# OutputDigital.net
KiCad netlist of a schematic drawn in Altium Designer
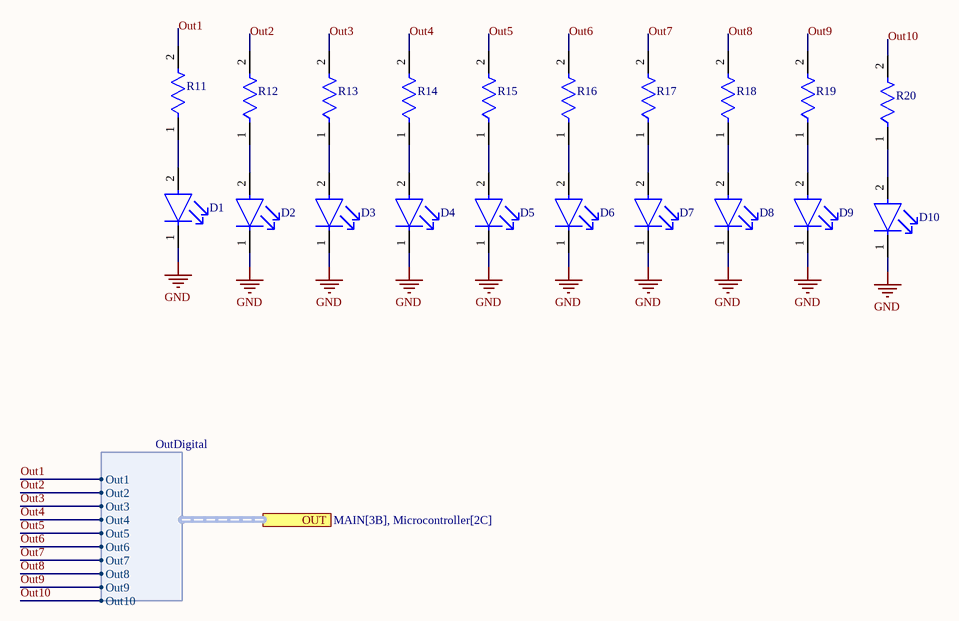
[diagram p0: OutputDigital.SchDoc]

(export (version "E")
  (design (tool "Eeschema 10.0.6"))
  (components
    (comp (ref "D1")
      (value "LTST-C230KRKT")
      (footprint "FP-LTST-C230KRKT-MFG")
      (description "LED RED CLEAR CHIP SMD")
      (libsource (lib "Ejemplo2") (part "CMP-22017-000041-1"))
    )
    (comp (ref "D2")
      (value "LTST-C230KRKT")
      (footprint "FP-LTST-C230KRKT-MFG")
      (description "LED RED CLEAR CHIP SMD")
      (libsource (lib "Ejemplo2") (part "CMP-22017-000041-1"))
    )
    (comp (ref "D3")
      (value "LTST-C230KRKT")
      (footprint "FP-LTST-C230KRKT-MFG")
      (description "LED RED CLEAR CHIP SMD")
      (libsource (lib "Ejemplo2") (part "CMP-22017-000041-1"))
    )
    (comp (ref "D4")
      (value "LTST-C230KRKT")
      (footprint "FP-LTST-C230KRKT-MFG")
      (description "LED RED CLEAR CHIP SMD")
      (libsource (lib "Ejemplo2") (part "CMP-22017-000041-1"))
    )
    (comp (ref "D5")
      (value "LTST-C230KRKT")
      (footprint "FP-LTST-C230KRKT-MFG")
      (description "LED RED CLEAR CHIP SMD")
      (libsource (lib "Ejemplo2") (part "CMP-22017-000041-1"))
    )
    (comp (ref "D6")
      (value "LTST-C230KRKT")
      (footprint "FP-LTST-C230KRKT-MFG")
      (description "LED RED CLEAR CHIP SMD")
      (libsource (lib "Ejemplo2") (part "CMP-22017-000041-1"))
    )
    (comp (ref "D7")
      (value "LTST-C230KRKT")
      (footprint "FP-LTST-C230KRKT-MFG")
      (description "LED RED CLEAR CHIP SMD")
      (libsource (lib "Ejemplo2") (part "CMP-22017-000041-1"))
    )
    (comp (ref "D8")
      (value "LTST-C230KRKT")
      (footprint "FP-LTST-C230KRKT-MFG")
      (description "LED RED CLEAR CHIP SMD")
      (libsource (lib "Ejemplo2") (part "CMP-22017-000041-1"))
    )
    (comp (ref "D9")
      (value "LTST-C230KRKT")
      (footprint "FP-LTST-C230KRKT-MFG")
      (description "LED RED CLEAR CHIP SMD")
      (libsource (lib "Ejemplo2") (part "CMP-22017-000041-1"))
    )
    (comp (ref "D10")
      (value "LTST-C230KRKT")
      (footprint "FP-LTST-C230KRKT-MFG")
      (description "LED RED CLEAR CHIP SMD")
      (libsource (lib "Ejemplo2") (part "CMP-22017-000041-1"))
    )
    (comp (ref "R11")
      (value "RT0805BRD07249RL")
      (footprint "FP-RT0805-MFG")
      (description "RES SMD 249 OHM 0.1% 1/8W 0805")
      (fields
        (field (name "OCTOPART") "https://octopart.com/rt0805brd07249rl-yageo-1410573")
        (field (name "MANUFACTURER") "Yageo")
      )
      (libsource (lib "Ejemplo2") (part "CMP-03412-035801-1"))
    )
    (comp (ref "R12")
      (value "RT0805BRD07249RL")
      (footprint "FP-RT0805-MFG")
      (description "RES SMD 249 OHM 0.1% 1/8W 0805")
      (fields
        (field (name "OCTOPART") "https://octopart.com/rt0805brd07249rl-yageo-1410573")
        (field (name "MANUFACTURER") "Yageo")
      )
      (libsource (lib "Ejemplo2") (part "CMP-03412-035801-1"))
    )
    (comp (ref "R13")
      (value "RT0805BRD07249RL")
      (footprint "FP-RT0805-MFG")
      (description "RES SMD 249 OHM 0.1% 1/8W 0805")
      (fields
        (field (name "OCTOPART") "https://octopart.com/rt0805brd07249rl-yageo-1410573")
        (field (name "MANUFACTURER") "Yageo")
      )
      (libsource (lib "Ejemplo2") (part "CMP-03412-035801-1"))
    )
    (comp (ref "R14")
      (value "RT0805BRD07249RL")
      (footprint "FP-RT0805-MFG")
      (description "RES SMD 249 OHM 0.1% 1/8W 0805")
      (fields
        (field (name "OCTOPART") "https://octopart.com/rt0805brd07249rl-yageo-1410573")
        (field (name "MANUFACTURER") "Yageo")
      )
      (libsource (lib "Ejemplo2") (part "CMP-03412-035801-1"))
    )
    (comp (ref "R15")
      (value "RT0805BRD07249RL")
      (footprint "FP-RT0805-MFG")
      (description "RES SMD 249 OHM 0.1% 1/8W 0805")
      (fields
        (field (name "OCTOPART") "https://octopart.com/rt0805brd07249rl-yageo-1410573")
        (field (name "MANUFACTURER") "Yageo")
      )
      (libsource (lib "Ejemplo2") (part "CMP-03412-035801-1"))
    )
    (comp (ref "R16")
      (value "RT0805BRD07249RL")
      (footprint "FP-RT0805-MFG")
      (description "RES SMD 249 OHM 0.1% 1/8W 0805")
      (fields
        (field (name "OCTOPART") "https://octopart.com/rt0805brd07249rl-yageo-1410573")
        (field (name "MANUFACTURER") "Yageo")
      )
      (libsource (lib "Ejemplo2") (part "CMP-03412-035801-1"))
    )
    (comp (ref "R17")
      (value "RT0805BRD07249RL")
      (footprint "FP-RT0805-MFG")
      (description "RES SMD 249 OHM 0.1% 1/8W 0805")
      (fields
        (field (name "OCTOPART") "https://octopart.com/rt0805brd07249rl-yageo-1410573")
        (field (name "MANUFACTURER") "Yageo")
      )
      (libsource (lib "Ejemplo2") (part "CMP-03412-035801-1"))
    )
    (comp (ref "R18")
      (value "RT0805BRD07249RL")
      (footprint "FP-RT0805-MFG")
      (description "RES SMD 249 OHM 0.1% 1/8W 0805")
      (fields
        (field (name "OCTOPART") "https://octopart.com/rt0805brd07249rl-yageo-1410573")
        (field (name "MANUFACTURER") "Yageo")
      )
      (libsource (lib "Ejemplo2") (part "CMP-03412-035801-1"))
    )
    (comp (ref "R19")
      (value "RT0805BRD07249RL")
      (footprint "FP-RT0805-MFG")
      (description "RES SMD 249 OHM 0.1% 1/8W 0805")
      (fields
        (field (name "OCTOPART") "https://octopart.com/rt0805brd07249rl-yageo-1410573")
        (field (name "MANUFACTURER") "Yageo")
      )
      (libsource (lib "Ejemplo2") (part "CMP-03412-035801-1"))
    )
    (comp (ref "R20")
      (value "RT0805BRD07249RL")
      (footprint "FP-RT0805-MFG")
      (description "RES SMD 249 OHM 0.1% 1/8W 0805")
      (fields
        (field (name "OCTOPART") "https://octopart.com/rt0805brd07249rl-yageo-1410573")
        (field (name "MANUFACTURER") "Yageo")
      )
      (libsource (lib "Ejemplo2") (part "CMP-03412-035801-1"))
    )
  )
  (nets
    (net (code "2") (name "/Out1") (class "Default")
      (node (ref "R11") (pin "2") (pinfunction "2_2") (pintype "passive"))
    )
    (net (code "3") (name "/Out2") (class "Default")
      (node (ref "R12") (pin "2") (pinfunction "2_2") (pintype "passive"))
    )
    (net (code "4") (name "/Out3") (class "Default")
      (node (ref "R13") (pin "2") (pinfunction "2_2") (pintype "passive"))
    )
    (net (code "5") (name "/Out4") (class "Default")
      (node (ref "R14") (pin "2") (pinfunction "2_2") (pintype "passive"))
    )
    (net (code "6") (name "/Out5") (class "Default")
      (node (ref "R15") (pin "2") (pinfunction "2_2") (pintype "passive"))
    )
    (net (code "7") (name "/Out6") (class "Default")
      (node (ref "R16") (pin "2") (pinfunction "2_2") (pintype "passive"))
    )
    (net (code "8") (name "/Out7") (class "Default")
      (node (ref "R17") (pin "2") (pinfunction "2_2") (pintype "passive"))
    )
    (net (code "9") (name "/Out8") (class "Default")
      (node (ref "R18") (pin "2") (pinfunction "2_2") (pintype "passive"))
    )
    (net (code "10") (name "/Out9") (class "Default")
      (node (ref "R19") (pin "2") (pinfunction "2_2") (pintype "passive"))
    )
    (net (code "11") (name "/Out10") (class "Default")
      (node (ref "R20") (pin "2") (pinfunction "2_2") (pintype "passive"))
    )
    (net (code "13") (name "GND") (class "Default")
      (node (ref "D1") (pin "1") (pinfunction "C_1") (pintype "passive"))
      (node (ref "D10") (pin "1") (pinfunction "C_1") (pintype "passive"))
      (node (ref "D2") (pin "1") (pinfunction "C_1") (pintype "passive"))
      (node (ref "D3") (pin "1") (pinfunction "C_1") (pintype "passive"))
      (node (ref "D4") (pin "1") (pinfunction "C_1") (pintype "passive"))
      (node (ref "D5") (pin "1") (pinfunction "C_1") (pintype "passive"))
      (node (ref "D6") (pin "1") (pinfunction "C_1") (pintype "passive"))
      (node (ref "D7") (pin "1") (pinfunction "C_1") (pintype "passive"))
      (node (ref "D8") (pin "1") (pinfunction "C_1") (pintype "passive"))
      (node (ref "D9") (pin "1") (pinfunction "C_1") (pintype "passive"))
    )
    (net (code "14") (name "Net-(D1-A)") (class "Default")
      (node (ref "D1") (pin "2") (pinfunction "A_2") (pintype "passive"))
      (node (ref "R11") (pin "1") (pinfunction "1_1") (pintype "passive"))
    )
    (net (code "15") (name "Net-(D2-A)") (class "Default")
      (node (ref "D2") (pin "2") (pinfunction "A_2") (pintype "passive"))
      (node (ref "R12") (pin "1") (pinfunction "1_1") (pintype "passive"))
    )
    (net (code "16") (name "Net-(D3-A)") (class "Default")
      (node (ref "D3") (pin "2") (pinfunction "A_2") (pintype "passive"))
      (node (ref "R13") (pin "1") (pinfunction "1_1") (pintype "passive"))
    )
    (net (code "17") (name "Net-(D4-A)") (class "Default")
      (node (ref "D4") (pin "2") (pinfunction "A_2") (pintype "passive"))
      (node (ref "R14") (pin "1") (pinfunction "1_1") (pintype "passive"))
    )
    (net (code "18") (name "Net-(D5-A)") (class "Default")
      (node (ref "D5") (pin "2") (pinfunction "A_2") (pintype "passive"))
      (node (ref "R15") (pin "1") (pinfunction "1_1") (pintype "passive"))
    )
    (net (code "19") (name "Net-(D6-A)") (class "Default")
      (node (ref "D6") (pin "2") (pinfunction "A_2") (pintype "passive"))
      (node (ref "R16") (pin "1") (pinfunction "1_1") (pintype "passive"))
    )
    (net (code "20") (name "Net-(D7-A)") (class "Default")
      (node (ref "D7") (pin "2") (pinfunction "A_2") (pintype "passive"))
      (node (ref "R17") (pin "1") (pinfunction "1_1") (pintype "passive"))
    )
    (net (code "21") (name "Net-(D8-A)") (class "Default")
      (node (ref "D8") (pin "2") (pinfunction "A_2") (pintype "passive"))
      (node (ref "R18") (pin "1") (pinfunction "1_1") (pintype "passive"))
    )
    (net (code "22") (name "Net-(D9-A)") (class "Default")
      (node (ref "D9") (pin "2") (pinfunction "A_2") (pintype "passive"))
      (node (ref "R19") (pin "1") (pinfunction "1_1") (pintype "passive"))
    )
    (net (code "23") (name "Net-(D10-A)") (class "Default")
      (node (ref "D10") (pin "2") (pinfunction "A_2") (pintype "passive"))
      (node (ref "R20") (pin "1") (pinfunction "1_1") (pintype "passive"))
    )
  )
)
